# 120V_Inverter_Power_Supply.net
KiCad netlist of a schematic drawn in EAGLE
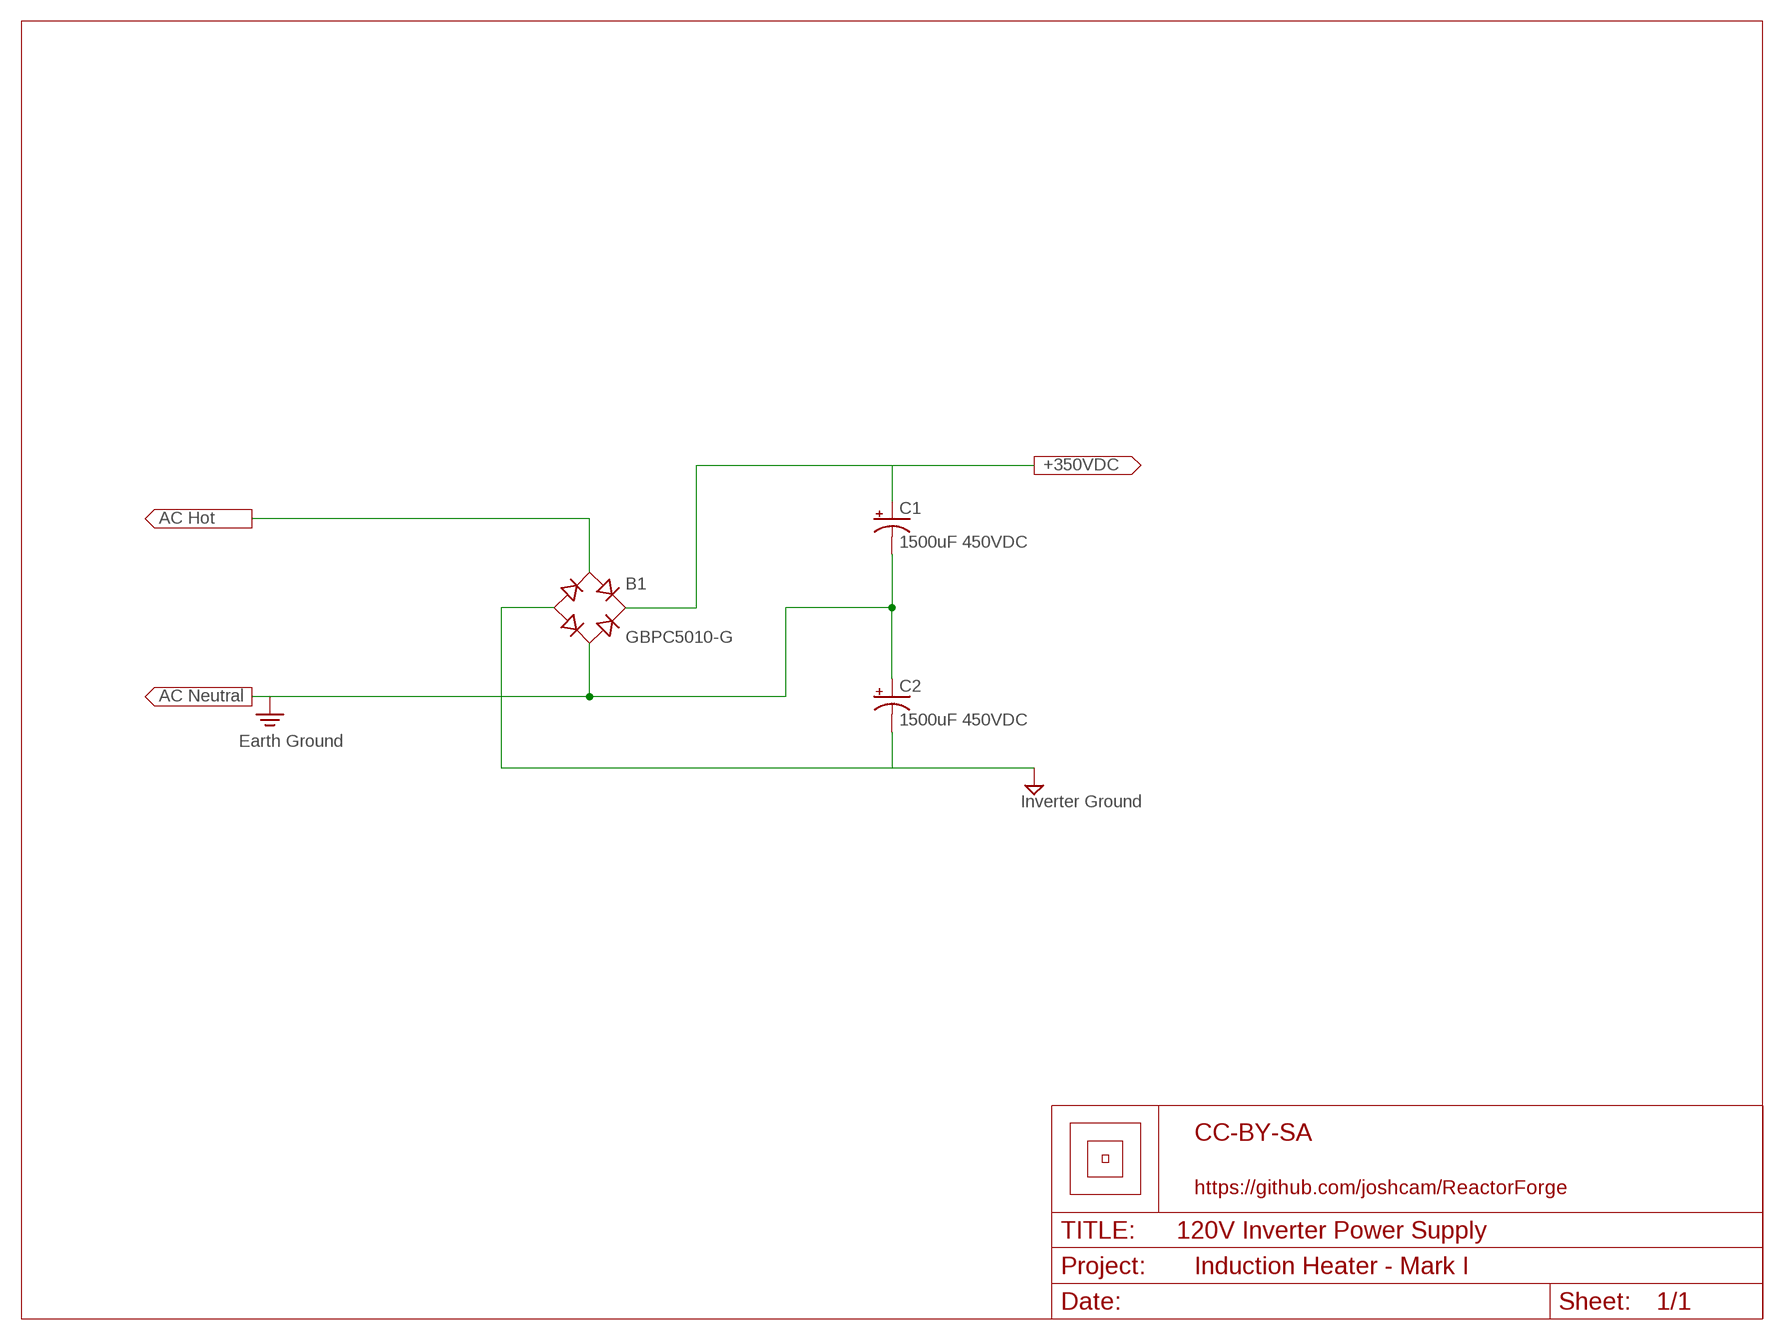
[diagram p0: schematic, sheet 1]

(export (version "E")
  (design (tool "Eeschema 10.0.6"))
  (components
    (comp (ref "B1")
      (value "GBPC5010-G")
      (footprint "eagle-import:DB")
      (libsource (lib "eagle-import") (part "DB?GDB101"))
    )
    (comp (ref "C1")
      (value "1500uF 450VDC")
      (footprint "eagle-import:EB35D")
      (libsource (lib "eagle-import") (part "CPOL-USE10-35"))
    )
    (comp (ref "C2")
      (value "1500uF 450VDC")
      (footprint "eagle-import:EB35D")
      (libsource (lib "eagle-import") (part "CPOL-USE10-35"))
    )
  )
  (nets
    (net (code "1") (name "Earth Ground") (class "Default")
      (node (ref "B1") (pin "AC2") (pinfunction "AC2_AC2") (pintype "passive"))
      (node (ref "C1") (pin "-") (pinfunction "-_-") (pintype "passive"))
      (node (ref "C2") (pin "+") (pinfunction "+_+") (pintype "passive"))
    )
    (net (code "2") (name "Inverter Ground") (class "Default")
      (node (ref "B1") (pin "-") (pinfunction "-_-") (pintype "passive"))
      (node (ref "C2") (pin "-") (pinfunction "-_-") (pintype "passive"))
    )
    (net (code "3") (name "Net-(B1-Pad+)") (class "Default")
      (node (ref "B1") (pin "+") (pinfunction "+_+") (pintype "passive"))
      (node (ref "C1") (pin "+") (pinfunction "+_+") (pintype "passive"))
    )
    (net (code "4") (name "unconnected-(B1-PadAC1)") (class "Default")
      (node (ref "B1") (pin "AC1") (pinfunction "AC1_AC1") (pintype "passive"))
    )
  )
)
